# ponteH_terza.net
KiCad netlist of a schematic drawn in EAGLE
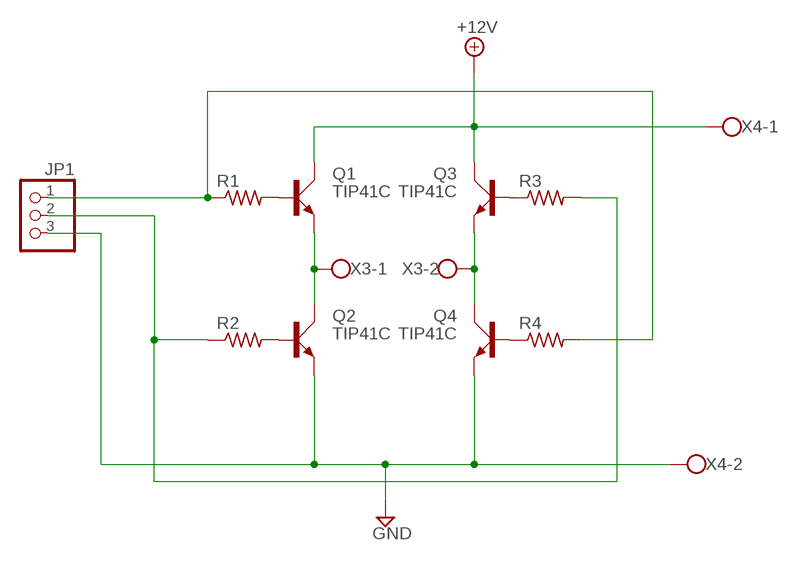
[diagram p0: schematic, sheet 1]

(export (version "E")
  (design (tool "Eeschema 10.0.6"))
  (components
    (comp (ref "JP1")
      (value "PINHD-1X3")
      (footprint "eagle-import:1X03")
      (libsource (lib "eagle-import") (part "PINHD-1X3"))
    )
    (comp (ref "Q1")
      (value "TIP41C")
      (footprint "eagle-import:TO220AV")
      (libsource (lib "eagle-import") (part "TIP41C"))
    )
    (comp (ref "Q2")
      (value "TIP41C")
      (footprint "eagle-import:TO220AV")
      (libsource (lib "eagle-import") (part "TIP41C"))
    )
    (comp (ref "Q3")
      (value "TIP41C")
      (footprint "eagle-import:TO220AV")
      (libsource (lib "eagle-import") (part "TIP41C"))
    )
    (comp (ref "Q4")
      (value "TIP41C")
      (footprint "eagle-import:TO220AV")
      (libsource (lib "eagle-import") (part "TIP41C"))
    )
    (comp (ref "R1")
      (value "R-US_0207/10")
      (footprint "eagle-import:0207_10")
      (libsource (lib "eagle-import") (part "R-US_0207/10"))
    )
    (comp (ref "R2")
      (value "R-US_0207/10")
      (footprint "eagle-import:0207_10")
      (libsource (lib "eagle-import") (part "R-US_0207/10"))
    )
    (comp (ref "R3")
      (value "R-US_0207/10")
      (footprint "eagle-import:0207_10")
      (libsource (lib "eagle-import") (part "R-US_0207/10"))
    )
    (comp (ref "R4")
      (value "R-US_0207/10")
      (footprint "eagle-import:0207_10")
      (libsource (lib "eagle-import") (part "R-US_0207/10"))
    )
    (comp (ref "X3")
      (value "W237-02P")
      (footprint "eagle-import:W237-132")
      (libsource (lib "eagle-import") (part "W237-02P"))
    )
    (comp (ref "X4")
      (value "W237-02P")
      (footprint "eagle-import:W237-132")
      (libsource (lib "eagle-import") (part "W237-02P"))
    )
  )
  (nets
    (net (code "1") (name "+12V") (class "Default")
      (node (ref "Q1") (pin "C") (pinfunction "C_C") (pintype "passive"))
      (node (ref "Q3") (pin "C") (pinfunction "C_C") (pintype "passive"))
      (node (ref "X4") (pin "1") (pinfunction "KL_1") (pintype "passive"))
    )
    (net (code "2") (name "GND") (class "Default")
      (node (ref "JP1") (pin "3") (pinfunction "3_3") (pintype "passive"))
      (node (ref "Q2") (pin "E") (pinfunction "E_E") (pintype "passive"))
      (node (ref "Q4") (pin "E") (pinfunction "E_E") (pintype "passive"))
      (node (ref "X4") (pin "2") (pinfunction "KL_2") (pintype "passive"))
    )
    (net (code "3") (name "Net-(JP1-Pad1)") (class "Default")
      (node (ref "JP1") (pin "1") (pinfunction "1_1") (pintype "passive"))
      (node (ref "R1") (pin "1") (pinfunction "1_1") (pintype "passive"))
      (node (ref "R4") (pin "2") (pinfunction "2_2") (pintype "passive"))
    )
    (net (code "4") (name "Net-(JP1-Pad2)") (class "Default")
      (node (ref "JP1") (pin "2") (pinfunction "2_2") (pintype "passive"))
      (node (ref "R2") (pin "1") (pinfunction "1_1") (pintype "passive"))
      (node (ref "R3") (pin "2") (pinfunction "2_2") (pintype "passive"))
    )
    (net (code "5") (name "Net-(Q1-PadB)") (class "Default")
      (node (ref "Q1") (pin "B") (pinfunction "B_B") (pintype "passive"))
      (node (ref "R1") (pin "2") (pinfunction "2_2") (pintype "passive"))
    )
    (net (code "6") (name "Net-(Q2-PadB)") (class "Default")
      (node (ref "Q2") (pin "B") (pinfunction "B_B") (pintype "passive"))
      (node (ref "R2") (pin "2") (pinfunction "2_2") (pintype "passive"))
    )
    (net (code "7") (name "Net-(Q3-PadB)") (class "Default")
      (node (ref "Q3") (pin "B") (pinfunction "B_B") (pintype "passive"))
      (node (ref "R3") (pin "1") (pinfunction "1_1") (pintype "passive"))
    )
    (net (code "8") (name "Net-(Q4-PadB)") (class "Default")
      (node (ref "Q4") (pin "B") (pinfunction "B_B") (pintype "passive"))
      (node (ref "R4") (pin "1") (pinfunction "1_1") (pintype "passive"))
    )
    (net (code "9") (name "Net-(X3A-KL)") (class "Default")
      (node (ref "Q1") (pin "E") (pinfunction "E_E") (pintype "passive"))
      (node (ref "Q2") (pin "C") (pinfunction "C_C") (pintype "passive"))
      (node (ref "X3") (pin "1") (pinfunction "KL_1") (pintype "passive"))
    )
    (net (code "10") (name "Net-(X3B-KL)") (class "Default")
      (node (ref "Q3") (pin "E") (pinfunction "E_E") (pintype "passive"))
      (node (ref "Q4") (pin "C") (pinfunction "C_C") (pintype "passive"))
      (node (ref "X3") (pin "2") (pinfunction "KL_2") (pintype "passive"))
    )
  )
)
